# BitUCounter.net
KiCad netlist of a schematic drawn in EAGLE
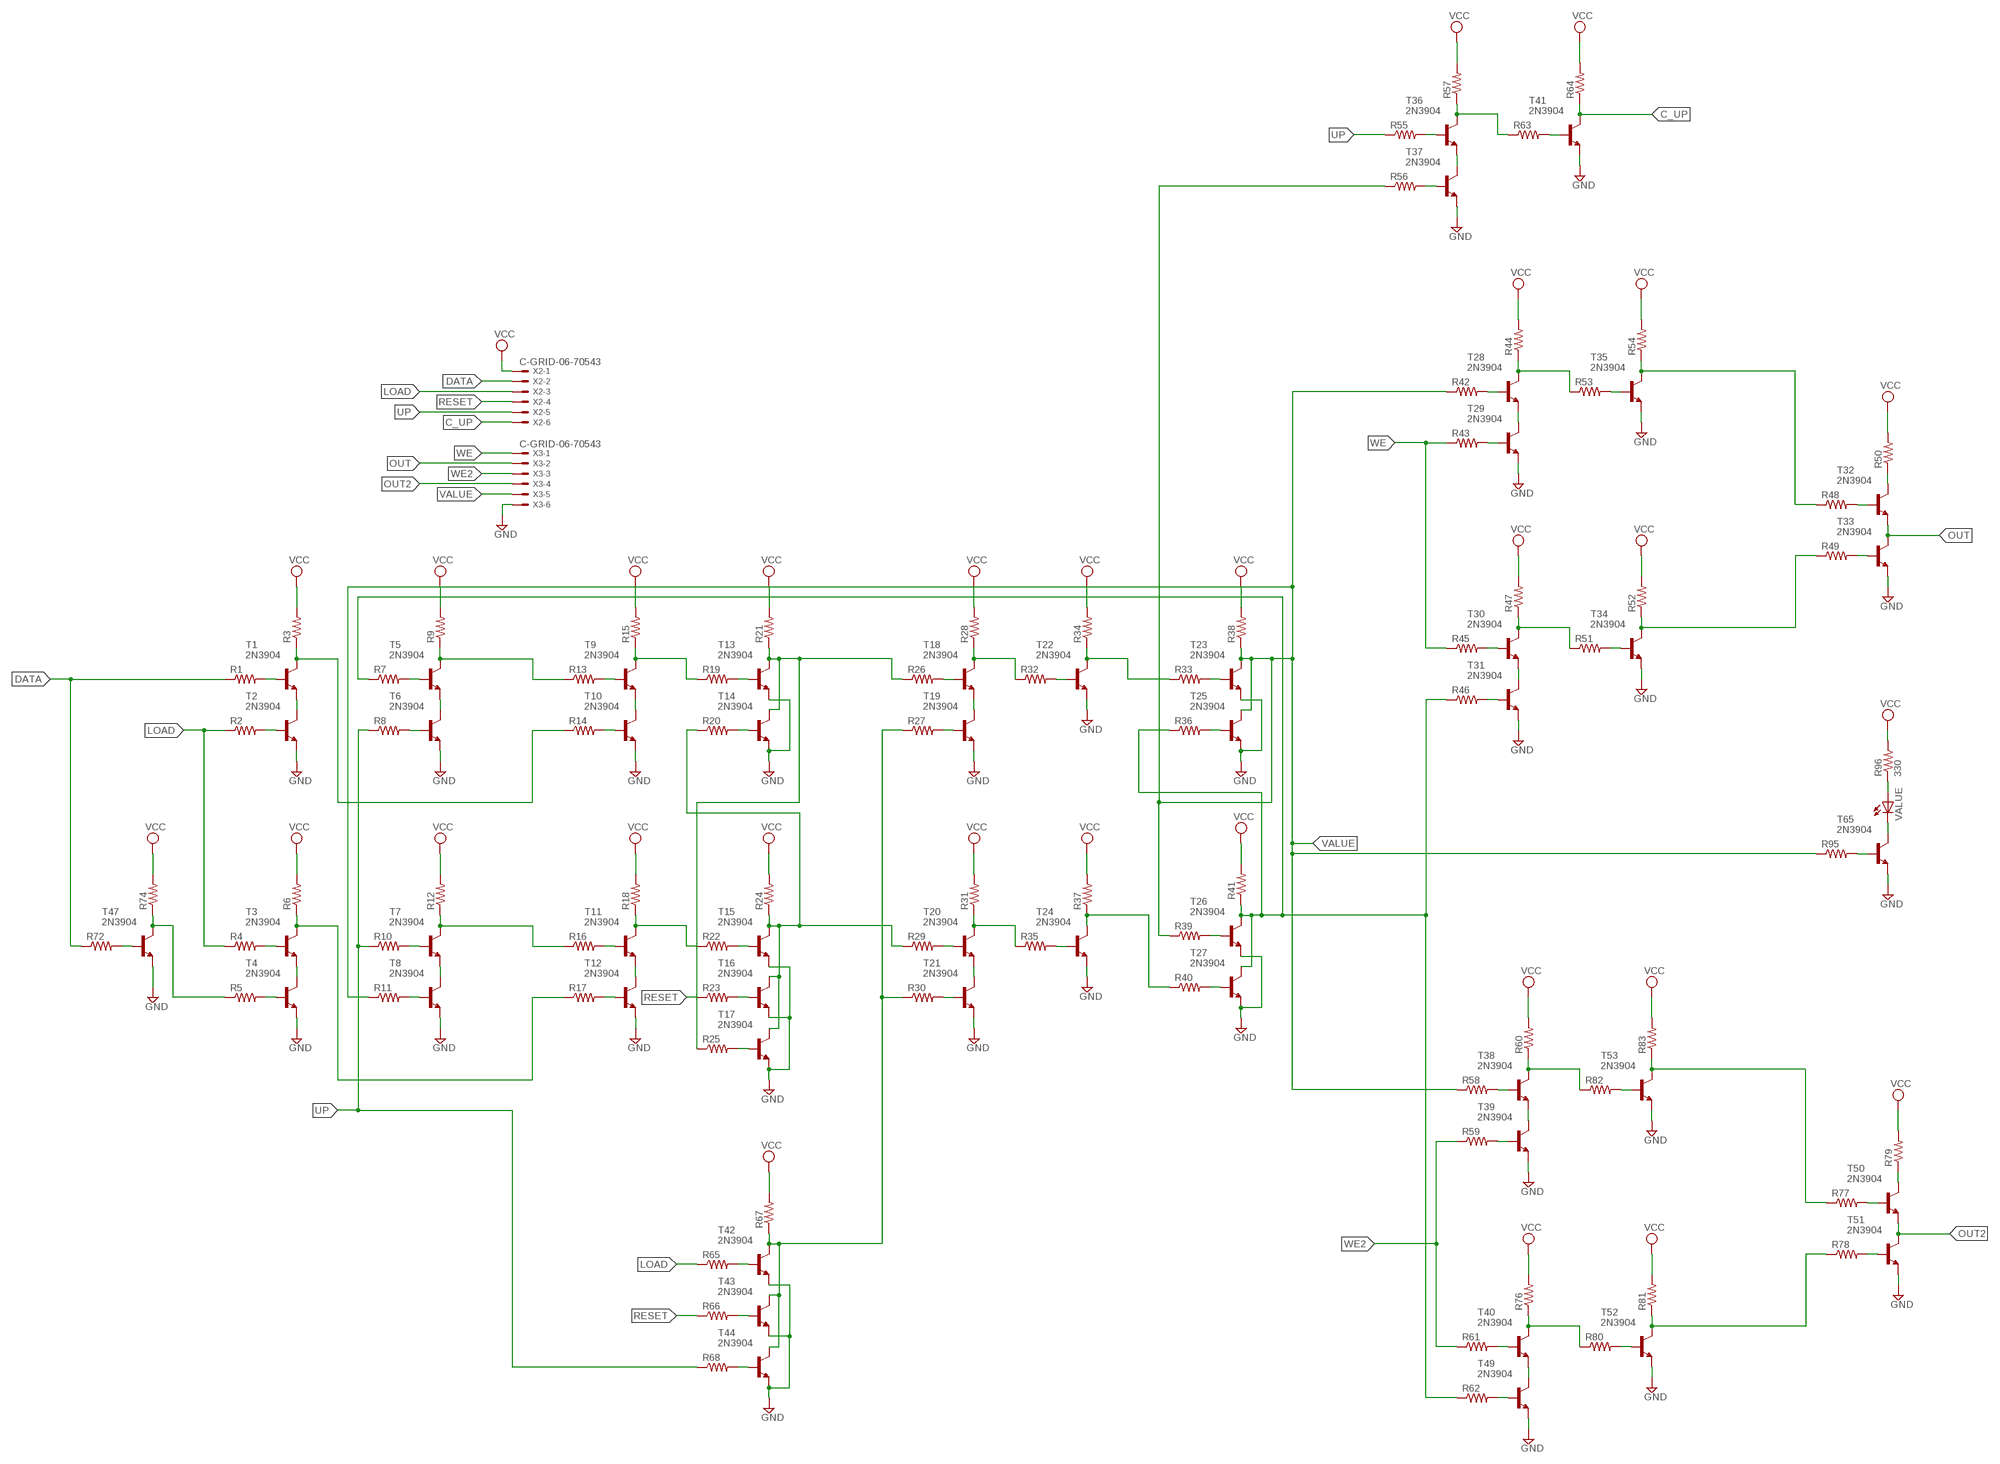
[diagram p0: schematic, sheet 1]

(export (version "E")
  (design (tool "Eeschema 10.0.6"))
  (components
    (comp (ref "R1")
      (value "R-US_0309/10")
      (footprint "eagle-import:0309_10")
      (libsource (lib "eagle-import") (part "R-US_0309/10"))
    )
    (comp (ref "R2")
      (value "R-US_0309/10")
      (footprint "eagle-import:0309_10")
      (libsource (lib "eagle-import") (part "R-US_0309/10"))
    )
    (comp (ref "R3")
      (value "R-US_0309/10")
      (footprint "eagle-import:0309_10")
      (libsource (lib "eagle-import") (part "R-US_0309/10"))
    )
    (comp (ref "R4")
      (value "R-US_0309/10")
      (footprint "eagle-import:0309_10")
      (libsource (lib "eagle-import") (part "R-US_0309/10"))
    )
    (comp (ref "R5")
      (value "R-US_0309/10")
      (footprint "eagle-import:0309_10")
      (libsource (lib "eagle-import") (part "R-US_0309/10"))
    )
    (comp (ref "R6")
      (value "R-US_0309/10")
      (footprint "eagle-import:0309_10")
      (libsource (lib "eagle-import") (part "R-US_0309/10"))
    )
    (comp (ref "R7")
      (value "R-US_0309/10")
      (footprint "eagle-import:0309_10")
      (libsource (lib "eagle-import") (part "R-US_0309/10"))
    )
    (comp (ref "R8")
      (value "R-US_0309/10")
      (footprint "eagle-import:0309_10")
      (libsource (lib "eagle-import") (part "R-US_0309/10"))
    )
    (comp (ref "R9")
      (value "R-US_0309/10")
      (footprint "eagle-import:0309_10")
      (libsource (lib "eagle-import") (part "R-US_0309/10"))
    )
    (comp (ref "R10")
      (value "R-US_0309/10")
      (footprint "eagle-import:0309_10")
      (libsource (lib "eagle-import") (part "R-US_0309/10"))
    )
    (comp (ref "R11")
      (value "R-US_0309/10")
      (footprint "eagle-import:0309_10")
      (libsource (lib "eagle-import") (part "R-US_0309/10"))
    )
    (comp (ref "R12")
      (value "R-US_0309/10")
      (footprint "eagle-import:0309_10")
      (libsource (lib "eagle-import") (part "R-US_0309/10"))
    )
    (comp (ref "R13")
      (value "R-US_0309/10")
      (footprint "eagle-import:0309_10")
      (libsource (lib "eagle-import") (part "R-US_0309/10"))
    )
    (comp (ref "R14")
      (value "R-US_0309/10")
      (footprint "eagle-import:0309_10")
      (libsource (lib "eagle-import") (part "R-US_0309/10"))
    )
    (comp (ref "R15")
      (value "R-US_0309/10")
      (footprint "eagle-import:0309_10")
      (libsource (lib "eagle-import") (part "R-US_0309/10"))
    )
    (comp (ref "R16")
      (value "R-US_0309/10")
      (footprint "eagle-import:0309_10")
      (libsource (lib "eagle-import") (part "R-US_0309/10"))
    )
    (comp (ref "R17")
      (value "R-US_0309/10")
      (footprint "eagle-import:0309_10")
      (libsource (lib "eagle-import") (part "R-US_0309/10"))
    )
    (comp (ref "R18")
      (value "R-US_0309/10")
      (footprint "eagle-import:0309_10")
      (libsource (lib "eagle-import") (part "R-US_0309/10"))
    )
    (comp (ref "R19")
      (value "R-US_0309/10")
      (footprint "eagle-import:0309_10")
      (libsource (lib "eagle-import") (part "R-US_0309/10"))
    )
    (comp (ref "R20")
      (value "R-US_0309/10")
      (footprint "eagle-import:0309_10")
      (libsource (lib "eagle-import") (part "R-US_0309/10"))
    )
    (comp (ref "R21")
      (value "R-US_0309/10")
      (footprint "eagle-import:0309_10")
      (libsource (lib "eagle-import") (part "R-US_0309/10"))
    )
    (comp (ref "R22")
      (value "R-US_0309/10")
      (footprint "eagle-import:0309_10")
      (libsource (lib "eagle-import") (part "R-US_0309/10"))
    )
    (comp (ref "R23")
      (value "R-US_0309/10")
      (footprint "eagle-import:0309_10")
      (libsource (lib "eagle-import") (part "R-US_0309/10"))
    )
    (comp (ref "R24")
      (value "R-US_0309/10")
      (footprint "eagle-import:0309_10")
      (libsource (lib "eagle-import") (part "R-US_0309/10"))
    )
    (comp (ref "R25")
      (value "R-US_0309/10")
      (footprint "eagle-import:0309_10")
      (libsource (lib "eagle-import") (part "R-US_0309/10"))
    )
    (comp (ref "R26")
      (value "R-US_0309/10")
      (footprint "eagle-import:0309_10")
      (libsource (lib "eagle-import") (part "R-US_0309/10"))
    )
    (comp (ref "R27")
      (value "R-US_0309/10")
      (footprint "eagle-import:0309_10")
      (libsource (lib "eagle-import") (part "R-US_0309/10"))
    )
    (comp (ref "R28")
      (value "R-US_0309/10")
      (footprint "eagle-import:0309_10")
      (libsource (lib "eagle-import") (part "R-US_0309/10"))
    )
    (comp (ref "R29")
      (value "R-US_0309/10")
      (footprint "eagle-import:0309_10")
      (libsource (lib "eagle-import") (part "R-US_0309/10"))
    )
    (comp (ref "R30")
      (value "R-US_0309/10")
      (footprint "eagle-import:0309_10")
      (libsource (lib "eagle-import") (part "R-US_0309/10"))
    )
    (comp (ref "R31")
      (value "R-US_0309/10")
      (footprint "eagle-import:0309_10")
      (libsource (lib "eagle-import") (part "R-US_0309/10"))
    )
    (comp (ref "R32")
      (value "R-US_0309/10")
      (footprint "eagle-import:0309_10")
      (libsource (lib "eagle-import") (part "R-US_0309/10"))
    )
    (comp (ref "R33")
      (value "R-US_0309/10")
      (footprint "eagle-import:0309_10")
      (libsource (lib "eagle-import") (part "R-US_0309/10"))
    )
    (comp (ref "R34")
      (value "R-US_0309/10")
      (footprint "eagle-import:0309_10")
      (libsource (lib "eagle-import") (part "R-US_0309/10"))
    )
    (comp (ref "R35")
      (value "R-US_0309/10")
      (footprint "eagle-import:0309_10")
      (libsource (lib "eagle-import") (part "R-US_0309/10"))
    )
    (comp (ref "R36")
      (value "R-US_0309/10")
      (footprint "eagle-import:0309_10")
      (libsource (lib "eagle-import") (part "R-US_0309/10"))
    )
    (comp (ref "R37")
      (value "R-US_0309/10")
      (footprint "eagle-import:0309_10")
      (libsource (lib "eagle-import") (part "R-US_0309/10"))
    )
    (comp (ref "R38")
      (value "R-US_0309/10")
      (footprint "eagle-import:0309_10")
      (libsource (lib "eagle-import") (part "R-US_0309/10"))
    )
    (comp (ref "R39")
      (value "R-US_0309/10")
      (footprint "eagle-import:0309_10")
      (libsource (lib "eagle-import") (part "R-US_0309/10"))
    )
    (comp (ref "R40")
      (value "R-US_0309/10")
      (footprint "eagle-import:0309_10")
      (libsource (lib "eagle-import") (part "R-US_0309/10"))
    )
    (comp (ref "R41")
      (value "R-US_0309/10")
      (footprint "eagle-import:0309_10")
      (libsource (lib "eagle-import") (part "R-US_0309/10"))
    )
    (comp (ref "R42")
      (value "R-US_0309/10")
      (footprint "eagle-import:0309_10")
      (libsource (lib "eagle-import") (part "R-US_0309/10"))
    )
    (comp (ref "R43")
      (value "R-US_0309/10")
      (footprint "eagle-import:0309_10")
      (libsource (lib "eagle-import") (part "R-US_0309/10"))
    )
    (comp (ref "R44")
      (value "R-US_0309/10")
      (footprint "eagle-import:0309_10")
      (libsource (lib "eagle-import") (part "R-US_0309/10"))
    )
    (comp (ref "R45")
      (value "R-US_0309/10")
      (footprint "eagle-import:0309_10")
      (libsource (lib "eagle-import") (part "R-US_0309/10"))
    )
    (comp (ref "R46")
      (value "R-US_0309/10")
      (footprint "eagle-import:0309_10")
      (libsource (lib "eagle-import") (part "R-US_0309/10"))
    )
    (comp (ref "R47")
      (value "R-US_0309/10")
      (footprint "eagle-import:0309_10")
      (libsource (lib "eagle-import") (part "R-US_0309/10"))
    )
    (comp (ref "R48")
      (value "R-US_0309/10")
      (footprint "eagle-import:0309_10")
      (libsource (lib "eagle-import") (part "R-US_0309/10"))
    )
    (comp (ref "R49")
      (value "R-US_0309/10")
      (footprint "eagle-import:0309_10")
      (libsource (lib "eagle-import") (part "R-US_0309/10"))
    )
    (comp (ref "R50")
      (value "R-US_0309/10")
      (footprint "eagle-import:0309_10")
      (libsource (lib "eagle-import") (part "R-US_0309/10"))
    )
    (comp (ref "R51")
      (value "R-US_0309/10")
      (footprint "eagle-import:0309_10")
      (libsource (lib "eagle-import") (part "R-US_0309/10"))
    )
    (comp (ref "R52")
      (value "R-US_0309/10")
      (footprint "eagle-import:0309_10")
      (libsource (lib "eagle-import") (part "R-US_0309/10"))
    )
    (comp (ref "R53")
      (value "R-US_0309/10")
      (footprint "eagle-import:0309_10")
      (libsource (lib "eagle-import") (part "R-US_0309/10"))
    )
    (comp (ref "R54")
      (value "R-US_0309/10")
      (footprint "eagle-import:0309_10")
      (libsource (lib "eagle-import") (part "R-US_0309/10"))
    )
    (comp (ref "R55")
      (value "R-US_0309/10")
      (footprint "eagle-import:0309_10")
      (libsource (lib "eagle-import") (part "R-US_0309/10"))
    )
    (comp (ref "R56")
      (value "R-US_0309/10")
      (footprint "eagle-import:0309_10")
      (libsource (lib "eagle-import") (part "R-US_0309/10"))
    )
    (comp (ref "R57")
      (value "R-US_0309/10")
      (footprint "eagle-import:0309_10")
      (libsource (lib "eagle-import") (part "R-US_0309/10"))
    )
    (comp (ref "R58")
      (value "R-US_0309/10")
      (footprint "eagle-import:0309_10")
      (libsource (lib "eagle-import") (part "R-US_0309/10"))
    )
    (comp (ref "R59")
      (value "R-US_0309/10")
      (footprint "eagle-import:0309_10")
      (libsource (lib "eagle-import") (part "R-US_0309/10"))
    )
    (comp (ref "R60")
      (value "R-US_0309/10")
      (footprint "eagle-import:0309_10")
      (libsource (lib "eagle-import") (part "R-US_0309/10"))
    )
    (comp (ref "R61")
      (value "R-US_0309/10")
      (footprint "eagle-import:0309_10")
      (libsource (lib "eagle-import") (part "R-US_0309/10"))
    )
    (comp (ref "R62")
      (value "R-US_0309/10")
      (footprint "eagle-import:0309_10")
      (libsource (lib "eagle-import") (part "R-US_0309/10"))
    )
    (comp (ref "R63")
      (value "R-US_0309/10")
      (footprint "eagle-import:0309_10")
      (libsource (lib "eagle-import") (part "R-US_0309/10"))
    )
    (comp (ref "R64")
      (value "R-US_0309/10")
      (footprint "eagle-import:0309_10")
      (libsource (lib "eagle-import") (part "R-US_0309/10"))
    )
    (comp (ref "R65")
      (value "R-US_0309/10")
      (footprint "eagle-import:0309_10")
      (libsource (lib "eagle-import") (part "R-US_0309/10"))
    )
    (comp (ref "R66")
      (value "R-US_0309/10")
      (footprint "eagle-import:0309_10")
      (libsource (lib "eagle-import") (part "R-US_0309/10"))
    )
    (comp (ref "R67")
      (value "R-US_0309/10")
      (footprint "eagle-import:0309_10")
      (libsource (lib "eagle-import") (part "R-US_0309/10"))
    )
    (comp (ref "R68")
      (value "R-US_0309/10")
      (footprint "eagle-import:0309_10")
      (libsource (lib "eagle-import") (part "R-US_0309/10"))
    )
    (comp (ref "R72")
      (value "R-US_0309/10")
      (footprint "eagle-import:0309_10")
      (libsource (lib "eagle-import") (part "R-US_0309/10"))
    )
    (comp (ref "R74")
      (value "R-US_0309/10")
      (footprint "eagle-import:0309_10")
      (libsource (lib "eagle-import") (part "R-US_0309/10"))
    )
    (comp (ref "R76")
      (value "R-US_0309/10")
      (footprint "eagle-import:0309_10")
      (libsource (lib "eagle-import") (part "R-US_0309/10"))
    )
    (comp (ref "R77")
      (value "R-US_0309/10")
      (footprint "eagle-import:0309_10")
      (libsource (lib "eagle-import") (part "R-US_0309/10"))
    )
    (comp (ref "R78")
      (value "R-US_0309/10")
      (footprint "eagle-import:0309_10")
      (libsource (lib "eagle-import") (part "R-US_0309/10"))
    )
    (comp (ref "R79")
      (value "R-US_0309/10")
      (footprint "eagle-import:0309_10")
      (libsource (lib "eagle-import") (part "R-US_0309/10"))
    )
    (comp (ref "R80")
      (value "R-US_0309/10")
      (footprint "eagle-import:0309_10")
      (libsource (lib "eagle-import") (part "R-US_0309/10"))
    )
    (comp (ref "R81")
      (value "R-US_0309/10")
      (footprint "eagle-import:0309_10")
      (libsource (lib "eagle-import") (part "R-US_0309/10"))
    )
    (comp (ref "R82")
      (value "R-US_0309/10")
      (footprint "eagle-import:0309_10")
      (libsource (lib "eagle-import") (part "R-US_0309/10"))
    )
    (comp (ref "R83")
      (value "R-US_0309/10")
      (footprint "eagle-import:0309_10")
      (libsource (lib "eagle-import") (part "R-US_0309/10"))
    )
    (comp (ref "R95")
      (value "R-US_0309/10")
      (footprint "eagle-import:0309_10")
      (libsource (lib "eagle-import") (part "R-US_0309/10"))
    )
    (comp (ref "R96")
      (value "330")
      (footprint "eagle-import:0309_10")
      (libsource (lib "eagle-import") (part "R-US_0309/10"))
    )
    (comp (ref "T1")
      (value "2N3904")
      (footprint "eagle-import:TO92")
      (libsource (lib "eagle-import") (part "2N3904"))
    )
    (comp (ref "T2")
      (value "2N3904")
      (footprint "eagle-import:TO92")
      (libsource (lib "eagle-import") (part "2N3904"))
    )
    (comp (ref "T3")
      (value "2N3904")
      (footprint "eagle-import:TO92")
      (libsource (lib "eagle-import") (part "2N3904"))
    )
    (comp (ref "T4")
      (value "2N3904")
      (footprint "eagle-import:TO92")
      (libsource (lib "eagle-import") (part "2N3904"))
    )
    (comp (ref "T5")
      (value "2N3904")
      (footprint "eagle-import:TO92")
      (libsource (lib "eagle-import") (part "2N3904"))
    )
    (comp (ref "T6")
      (value "2N3904")
      (footprint "eagle-import:TO92")
      (libsource (lib "eagle-import") (part "2N3904"))
    )
    (comp (ref "T7")
      (value "2N3904")
      (footprint "eagle-import:TO92")
      (libsource (lib "eagle-import") (part "2N3904"))
    )
    (comp (ref "T8")
      (value "2N3904")
      (footprint "eagle-import:TO92")
      (libsource (lib "eagle-import") (part "2N3904"))
    )
    (comp (ref "T9")
      (value "2N3904")
      (footprint "eagle-import:TO92")
      (libsource (lib "eagle-import") (part "2N3904"))
    )
    (comp (ref "T10")
      (value "2N3904")
      (footprint "eagle-import:TO92")
      (libsource (lib "eagle-import") (part "2N3904"))
    )
    (comp (ref "T11")
      (value "2N3904")
      (footprint "eagle-import:TO92")
      (libsource (lib "eagle-import") (part "2N3904"))
    )
    (comp (ref "T12")
      (value "2N3904")
      (footprint "eagle-import:TO92")
      (libsource (lib "eagle-import") (part "2N3904"))
    )
    (comp (ref "T13")
      (value "2N3904")
      (footprint "eagle-import:TO92")
      (libsource (lib "eagle-import") (part "2N3904"))
    )
    (comp (ref "T14")
      (value "2N3904")
      (footprint "eagle-import:TO92")
      (libsource (lib "eagle-import") (part "2N3904"))
    )
    (comp (ref "T15")
      (value "2N3904")
      (footprint "eagle-import:TO92")
      (libsource (lib "eagle-import") (part "2N3904"))
    )
    (comp (ref "T16")
      (value "2N3904")
      (footprint "eagle-import:TO92")
      (libsource (lib "eagle-import") (part "2N3904"))
    )
    (comp (ref "T17")
      (value "2N3904")
      (footprint "eagle-import:TO92")
      (libsource (lib "eagle-import") (part "2N3904"))
    )
    (comp (ref "T18")
      (value "2N3904")
      (footprint "eagle-import:TO92")
      (libsource (lib "eagle-import") (part "2N3904"))
    )
    (comp (ref "T19")
      (value "2N3904")
      (footprint "eagle-import:TO92")
      (libsource (lib "eagle-import") (part "2N3904"))
    )
    (comp (ref "T20")
      (value "2N3904")
      (footprint "eagle-import:TO92")
      (libsource (lib "eagle-import") (part "2N3904"))
    )
    (comp (ref "T21")
      (value "2N3904")
      (footprint "eagle-import:TO92")
      (libsource (lib "eagle-import") (part "2N3904"))
    )
    (comp (ref "T22")
      (value "2N3904")
      (footprint "eagle-import:TO92")
      (libsource (lib "eagle-import") (part "2N3904"))
    )
    (comp (ref "T23")
      (value "2N3904")
      (footprint "eagle-import:TO92")
      (libsource (lib "eagle-import") (part "2N3904"))
    )
    (comp (ref "T24")
      (value "2N3904")
      (footprint "eagle-import:TO92")
      (libsource (lib "eagle-import") (part "2N3904"))
    )
    (comp (ref "T25")
      (value "2N3904")
      (footprint "eagle-import:TO92")
      (libsource (lib "eagle-import") (part "2N3904"))
    )
    (comp (ref "T26")
      (value "2N3904")
      (footprint "eagle-import:TO92")
      (libsource (lib "eagle-import") (part "2N3904"))
    )
    (comp (ref "T27")
      (value "2N3904")
      (footprint "eagle-import:TO92")
      (libsource (lib "eagle-import") (part "2N3904"))
    )
    (comp (ref "T28")
      (value "2N3904")
      (footprint "eagle-import:TO92")
      (libsource (lib "eagle-import") (part "2N3904"))
    )
    (comp (ref "T29")
      (value "2N3904")
      (footprint "eagle-import:TO92")
      (libsource (lib "eagle-import") (part "2N3904"))
    )
    (comp (ref "T30")
      (value "2N3904")
      (footprint "eagle-import:TO92")
      (libsource (lib "eagle-import") (part "2N3904"))
    )
    (comp (ref "T31")
      (value "2N3904")
      (footprint "eagle-import:TO92")
      (libsource (lib "eagle-import") (part "2N3904"))
    )
    (comp (ref "T32")
      (value "2N3904")
      (footprint "eagle-import:TO92")
      (libsource (lib "eagle-import") (part "2N3904"))
    )
    (comp (ref "T33")
      (value "2N3904")
      (footprint "eagle-import:TO92")
      (libsource (lib "eagle-import") (part "2N3904"))
    )
    (comp (ref "T34")
      (value "2N3904")
      (footprint "eagle-import:TO92")
      (libsource (lib "eagle-import") (part "2N3904"))
    )
    (comp (ref "T35")
      (value "2N3904")
      (footprint "eagle-import:TO92")
      (libsource (lib "eagle-import") (part "2N3904"))
    )
    (comp (ref "T36")
      (value "2N3904")
      (footprint "eagle-import:TO92")
      (libsource (lib "eagle-import") (part "2N3904"))
    )
    (comp (ref "T37")
      (value "2N3904")
      (footprint "eagle-import:TO92")
      (libsource (lib "eagle-import") (part "2N3904"))
    )
    (comp (ref "T38")
      (value "2N3904")
      (footprint "eagle-import:TO92")
      (libsource (lib "eagle-import") (part "2N3904"))
    )
    (comp (ref "T39")
      (value "2N3904")
      (footprint "eagle-import:TO92")
      (libsource (lib "eagle-import") (part "2N3904"))
    )
    (comp (ref "T40")
      (value "2N3904")
      (footprint "eagle-import:TO92")
      (libsource (lib "eagle-import") (part "2N3904"))
    )
    (comp (ref "T41")
      (value "2N3904")
      (footprint "eagle-import:TO92")
      (libsource (lib "eagle-import") (part "2N3904"))
    )
    (comp (ref "T42")
      (value "2N3904")
      (footprint "eagle-import:TO92")
      (libsource (lib "eagle-import") (part "2N3904"))
    )
    (comp (ref "T43")
      (value "2N3904")
      (footprint "eagle-import:TO92")
      (libsource (lib "eagle-import") (part "2N3904"))
    )
    (comp (ref "T44")
      (value "2N3904")
      (footprint "eagle-import:TO92")
      (libsource (lib "eagle-import") (part "2N3904"))
    )
    (comp (ref "T47")
      (value "2N3904")
      (footprint "eagle-import:TO92")
      (libsource (lib "eagle-import") (part "2N3904"))
    )
    (comp (ref "T49")
      (value "2N3904")
      (footprint "eagle-import:TO92")
      (libsource (lib "eagle-import") (part "2N3904"))
    )
    (comp (ref "T50")
      (value "2N3904")
      (footprint "eagle-import:TO92")
      (libsource (lib "eagle-import") (part "2N3904"))
    )
    (comp (ref "T51")
      (value "2N3904")
      (footprint "eagle-import:TO92")
      (libsource (lib "eagle-import") (part "2N3904"))
    )
    (comp (ref "T52")
      (value "2N3904")
      (footprint "eagle-import:TO92")
      (libsource (lib "eagle-import") (part "2N3904"))
    )
    (comp (ref "T53")
      (value "2N3904")
      (footprint "eagle-import:TO92")
      (libsource (lib "eagle-import") (part "2N3904"))
    )
    (comp (ref "T65")
      (value "2N3904")
      (footprint "eagle-import:TO92")
      (libsource (lib "eagle-import") (part "2N3904"))
    )
    (comp (ref "VALUE")
      (value "LED5MM")
      (footprint "eagle-import:LED5MM")
      (libsource (lib "eagle-import") (part "LED5MM"))
    )
    (comp (ref "X2")
      (value "C-GRID-06-70543")
      (footprint "eagle-import:70543-06")
      (fields (field (name "MF") "MOLEX"))
      (libsource (lib "eagle-import") (part "C-GRID-06-70543"))
    )
    (comp (ref "X3")
      (value "C-GRID-06-70543")
      (footprint "eagle-import:70543-06")
      (fields (field (name "MF") "MOLEX"))
      (libsource (lib "eagle-import") (part "C-GRID-06-70543"))
    )
  )
  (nets
    (net (code "1") (name "C_UP") (class "Default")
      (node (ref "R64") (pin "1") (pinfunction "1_1") (pintype "passive"))
      (node (ref "T41") (pin "1") (pinfunction "C_1") (pintype "passive"))
      (node (ref "X2") (pin "6") (pinfunction "S_6") (pintype "passive"))
    )
    (net (code "2") (name "DATA") (class "Default")
      (node (ref "R1") (pin "1") (pinfunction "1_1") (pintype "passive"))
      (node (ref "R72") (pin "1") (pinfunction "1_1") (pintype "passive"))
      (node (ref "X2") (pin "2") (pinfunction "S_2") (pintype "passive"))
    )
    (net (code "3") (name "GND") (class "Default")
      (node (ref "T10") (pin "3") (pinfunction "E_3") (pintype "passive"))
      (node (ref "T12") (pin "3") (pinfunction "E_3") (pintype "passive"))
      (node (ref "T13") (pin "3") (pinfunction "E_3") (pintype "passive"))
      (node (ref "T14") (pin "3") (pinfunction "E_3") (pintype "passive"))
      (node (ref "T15") (pin "3") (pinfunction "E_3") (pintype "passive"))
      (node (ref "T16") (pin "3") (pinfunction "E_3") (pintype "passive"))
      (node (ref "T17") (pin "3") (pinfunction "E_3") (pintype "passive"))
      (node (ref "T19") (pin "3") (pinfunction "E_3") (pintype "passive"))
      (node (ref "T2") (pin "3") (pinfunction "E_3") (pintype "passive"))
      (node (ref "T21") (pin "3") (pinfunction "E_3") (pintype "passive"))
      (node (ref "T22") (pin "3") (pinfunction "E_3") (pintype "passive"))
      (node (ref "T23") (pin "3") (pinfunction "E_3") (pintype "passive"))
      (node (ref "T24") (pin "3") (pinfunction "E_3") (pintype "passive"))
      (node (ref "T25") (pin "3") (pinfunction "E_3") (pintype "passive"))
      (node (ref "T26") (pin "3") (pinfunction "E_3") (pintype "passive"))
      (node (ref "T27") (pin "3") (pinfunction "E_3") (pintype "passive"))
      (node (ref "T29") (pin "3") (pinfunction "E_3") (pintype "passive"))
      (node (ref "T31") (pin "3") (pinfunction "E_3") (pintype "passive"))
      (node (ref "T33") (pin "3") (pinfunction "E_3") (pintype "passive"))
      (node (ref "T34") (pin "3") (pinfunction "E_3") (pintype "passive"))
      (node (ref "T35") (pin "3") (pinfunction "E_3") (pintype "passive"))
      (node (ref "T37") (pin "3") (pinfunction "E_3") (pintype "passive"))
      (node (ref "T39") (pin "3") (pinfunction "E_3") (pintype "passive"))
      (node (ref "T4") (pin "3") (pinfunction "E_3") (pintype "passive"))
      (node (ref "T41") (pin "3") (pinfunction "E_3") (pintype "passive"))
      (node (ref "T42") (pin "3") (pinfunction "E_3") (pintype "passive"))
      (node (ref "T43") (pin "3") (pinfunction "E_3") (pintype "passive"))
      (node (ref "T44") (pin "3") (pinfunction "E_3") (pintype "passive"))
      (node (ref "T47") (pin "3") (pinfunction "E_3") (pintype "passive"))
      (node (ref "T49") (pin "3") (pinfunction "E_3") (pintype "passive"))
      (node (ref "T51") (pin "3") (pinfunction "E_3") (pintype "passive"))
      (node (ref "T52") (pin "3") (pinfunction "E_3") (pintype "passive"))
      (node (ref "T53") (pin "3") (pinfunction "E_3") (pintype "passive"))
      (node (ref "T6") (pin "3") (pinfunction "E_3") (pintype "passive"))
      (node (ref "T65") (pin "3") (pinfunction "E_3") (pintype "passive"))
      (node (ref "T8") (pin "3") (pinfunction "E_3") (pintype "passive"))
      (node (ref "X3") (pin "6") (pinfunction "S_6") (pintype "passive"))
    )
    (net (code "4") (name "LOAD") (class "Default")
      (node (ref "R2") (pin "1") (pinfunction "1_1") (pintype "passive"))
      (node (ref "R4") (pin "1") (pinfunction "1_1") (pintype "passive"))
      (node (ref "R65") (pin "1") (pinfunction "1_1") (pintype "passive"))
      (node (ref "X2") (pin "3") (pinfunction "S_3") (pintype "passive"))
    )
    (net (code "5") (name "Net-(R96-Pad1)") (class "Default")
      (node (ref "R96") (pin "1") (pinfunction "1_1") (pintype "passive"))
      (node (ref "VALUE") (pin "A") (pinfunction "A_A") (pintype "passive"))
    )
    (net (code "6") (name "Net-(T1-B)") (class "Default")
      (node (ref "R1") (pin "2") (pinfunction "2_2") (pintype "passive"))
      (node (ref "T1") (pin "2") (pinfunction "B_2") (pintype "passive"))
    )
    (net (code "7") (name "Net-(T1-C)") (class "Default")
      (node (ref "R14") (pin "1") (pinfunction "1_1") (pintype "passive"))
      (node (ref "R3") (pin "1") (pinfunction "1_1") (pintype "passive"))
      (node (ref "T1") (pin "1") (pinfunction "C_1") (pintype "passive"))
    )
    (net (code "8") (name "Net-(T1-E)") (class "Default")
      (node (ref "T1") (pin "3") (pinfunction "E_3") (pintype "passive"))
      (node (ref "T2") (pin "1") (pinfunction "C_1") (pintype "passive"))
    )
    (net (code "9") (name "Net-(T2-B)") (class "Default")
      (node (ref "R2") (pin "2") (pinfunction "2_2") (pintype "passive"))
      (node (ref "T2") (pin "2") (pinfunction "B_2") (pintype "passive"))
    )
    (net (code "10") (name "Net-(T3-B)") (class "Default")
      (node (ref "R4") (pin "2") (pinfunction "2_2") (pintype "passive"))
      (node (ref "T3") (pin "2") (pinfunction "B_2") (pintype "passive"))
    )
    (net (code "11") (name "Net-(T3-C)") (class "Default")
      (node (ref "R17") (pin "1") (pinfunction "1_1") (pintype "passive"))
      (node (ref "R6") (pin "1") (pinfunction "1_1") (pintype "passive"))
      (node (ref "T3") (pin "1") (pinfunction "C_1") (pintype "passive"))
    )
    (net (code "12") (name "Net-(T3-E)") (class "Default")
      (node (ref "T3") (pin "3") (pinfunction "E_3") (pintype "passive"))
      (node (ref "T4") (pin "1") (pinfunction "C_1") (pintype "passive"))
    )
    (net (code "13") (name "Net-(T4-B)") (class "Default")
      (node (ref "R5") (pin "2") (pinfunction "2_2") (pintype "passive"))
      (node (ref "T4") (pin "2") (pinfunction "B_2") (pintype "passive"))
    )
    (net (code "14") (name "Net-(T5-B)") (class "Default")
      (node (ref "R7") (pin "2") (pinfunction "2_2") (pintype "passive"))
      (node (ref "T5") (pin "2") (pinfunction "B_2") (pintype "passive"))
    )
    (net (code "15") (name "Net-(T5-C)") (class "Default")
      (node (ref "R13") (pin "1") (pinfunction "1_1") (pintype "passive"))
      (node (ref "R9") (pin "1") (pinfunction "1_1") (pintype "passive"))
      (node (ref "T5") (pin "1") (pinfunction "C_1") (pintype "passive"))
    )
    (net (code "16") (name "Net-(T5-E)") (class "Default")
      (node (ref "T5") (pin "3") (pinfunction "E_3") (pintype "passive"))
      (node (ref "T6") (pin "1") (pinfunction "C_1") (pintype "passive"))
    )
    (net (code "17") (name "Net-(T6-B)") (class "Default")
      (node (ref "R8") (pin "2") (pinfunction "2_2") (pintype "passive"))
      (node (ref "T6") (pin "2") (pinfunction "B_2") (pintype "passive"))
    )
    (net (code "18") (name "Net-(T7-B)") (class "Default")
      (node (ref "R10") (pin "2") (pinfunction "2_2") (pintype "passive"))
      (node (ref "T7") (pin "2") (pinfunction "B_2") (pintype "passive"))
    )
    (net (code "19") (name "Net-(T7-C)") (class "Default")
      (node (ref "R12") (pin "1") (pinfunction "1_1") (pintype "passive"))
      (node (ref "R16") (pin "1") (pinfunction "1_1") (pintype "passive"))
      (node (ref "T7") (pin "1") (pinfunction "C_1") (pintype "passive"))
    )
    (net (code "20") (name "Net-(T7-E)") (class "Default")
      (node (ref "T7") (pin "3") (pinfunction "E_3") (pintype "passive"))
      (node (ref "T8") (pin "1") (pinfunction "C_1") (pintype "passive"))
    )
    (net (code "21") (name "Net-(T8-B)") (class "Default")
      (node (ref "R11") (pin "2") (pinfunction "2_2") (pintype "passive"))
      (node (ref "T8") (pin "2") (pinfunction "B_2") (pintype "passive"))
    )
    (net (code "22") (name "Net-(T9-B)") (class "Default")
      (node (ref "R13") (pin "2") (pinfunction "2_2") (pintype "passive"))
      (node (ref "T9") (pin "2") (pinfunction "B_2") (pintype "passive"))
    )
    (net (code "23") (name "Net-(T9-C)") (class "Default")
      (node (ref "R15") (pin "1") (pinfunction "1_1") (pintype "passive"))
      (node (ref "R19") (pin "1") (pinfunction "1_1") (pintype "passive"))
      (node (ref "T9") (pin "1") (pinfunction "C_1") (pintype "passive"))
    )
    (net (code "24") (name "Net-(T10-B)") (class "Default")
      (node (ref "R14") (pin "2") (pinfunction "2_2") (pintype "passive"))
      (node (ref "T10") (pin "2") (pinfunction "B_2") (pintype "passive"))
    )
    (net (code "25") (name "Net-(T10-C)") (class "Default")
      (node (ref "T10") (pin "1") (pinfunction "C_1") (pintype "passive"))
      (node (ref "T9") (pin "3") (pinfunction "E_3") (pintype "passive"))
    )
    (net (code "26") (name "Net-(T11-B)") (class "Default")
      (node (ref "R16") (pin "2") (pinfunction "2_2") (pintype "passive"))
      (node (ref "T11") (pin "2") (pinfunction "B_2") (pintype "passive"))
    )
    (net (code "27") (name "Net-(T11-C)") (class "Default")
      (node (ref "R18") (pin "1") (pinfunction "1_1") (pintype "passive"))
      (node (ref "R22") (pin "1") (pinfunction "1_1") (pintype "passive"))
      (node (ref "T11") (pin "1") (pinfunction "C_1") (pintype "passive"))
    )
    (net (code "28") (name "Net-(T11-E)") (class "Default")
      (node (ref "T11") (pin "3") (pinfunction "E_3") (pintype "passive"))
      (node (ref "T12") (pin "1") (pinfunction "C_1") (pintype "passive"))
    )
    (net (code "29") (name "Net-(T12-B)") (class "Default")
      (node (ref "R17") (pin "2") (pinfunction "2_2") (pintype "passive"))
      (node (ref "T12") (pin "2") (pinfunction "B_2") (pintype "passive"))
    )
    (net (code "30") (name "Net-(T13-B)") (class "Default")
      (node (ref "R19") (pin "2") (pinfunction "2_2") (pintype "passive"))
      (node (ref "T13") (pin "2") (pinfunction "B_2") (pintype "passive"))
    )
    (net (code "31") (name "Net-(T13-C)") (class "Default")
      (node (ref "R21") (pin "1") (pinfunction "1_1") (pintype "passive"))
      (node (ref "R25") (pin "1") (pinfunction "1_1") (pintype "passive"))
      (node (ref "R26") (pin "1") (pinfunction "1_1") (pintype "passive"))
      (node (ref "T13") (pin "1") (pinfunction "C_1") (pintype "passive"))
      (node (ref "T14") (pin "1") (pinfunction "C_1") (pintype "passive"))
    )
    (net (code "32") (name "Net-(T14-B)") (class "Default")
      (node (ref "R20") (pin "2") (pinfunction "2_2") (pintype "passive"))
      (node (ref "T14") (pin "2") (pinfunction "B_2") (pintype "passive"))
    )
    (net (code "33") (name "Net-(T15-B)") (class "Default")
      (node (ref "R22") (pin "2") (pinfunction "2_2") (pintype "passive"))
      (node (ref "T15") (pin "2") (pinfunction "B_2") (pintype "passive"))
    )
    (net (code "34") (name "Net-(T15-C)") (class "Default")
      (node (ref "R20") (pin "1") (pinfunction "1_1") (pintype "passive"))
      (node (ref "R24") (pin "1") (pinfunction "1_1") (pintype "passive"))
      (node (ref "R29") (pin "1") (pinfunction "1_1") (pintype "passive"))
      (node (ref "T15") (pin "1") (pinfunction "C_1") (pintype "passive"))
      (node (ref "T16") (pin "1") (pinfunction "C_1") (pintype "passive"))
      (node (ref "T17") (pin "1") (pinfunction "C_1") (pintype "passive"))
    )
    (net (code "35") (name "Net-(T16-B)") (class "Default")
      (node (ref "R23") (pin "2") (pinfunction "2_2") (pintype "passive"))
      (node (ref "T16") (pin "2") (pinfunction "B_2") (pintype "passive"))
    )
    (net (code "36") (name "Net-(T17-B)") (class "Default")
      (node (ref "R25") (pin "2") (pinfunction "2_2") (pintype "passive"))
      (node (ref "T17") (pin "2") (pinfunction "B_2") (pintype "passive"))
    )
    (net (code "37") (name "Net-(T18-B)") (class "Default")
      (node (ref "R26") (pin "2") (pinfunction "2_2") (pintype "passive"))
      (node (ref "T18") (pin "2") (pinfunction "B_2") (pintype "passive"))
    )
    (net (code "38") (name "Net-(T18-C)") (class "Default")
      (node (ref "R28") (pin "1") (pinfunction "1_1") (pintype "passive"))
      (node (ref "R32") (pin "1") (pinfunction "1_1") (pintype "passive"))
      (node (ref "T18") (pin "1") (pinfunction "C_1") (pintype "passive"))
    )
    (net (code "39") (name "Net-(T18-E)") (class "Default")
      (node (ref "T18") (pin "3") (pinfunction "E_3") (pintype "passive"))
      (node (ref "T19") (pin "1") (pinfunction "C_1") (pintype "passive"))
    )
    (net (code "40") (name "Net-(T19-B)") (class "Default")
      (node (ref "R27") (pin "2") (pinfunction "2_2") (pintype "passive"))
      (node (ref "T19") (pin "2") (pinfunction "B_2") (pintype "passive"))
    )
    (net (code "41") (name "Net-(T20-B)") (class "Default")
      (node (ref "R29") (pin "2") (pinfunction "2_2") (pintype "passive"))
      (node (ref "T20") (pin "2") (pinfunction "B_2") (pintype "passive"))
    )
    (net (code "42") (name "Net-(T20-C)") (class "Default")
      (node (ref "R31") (pin "1") (pinfunction "1_1") (pintype "passive"))
      (node (ref "R35") (pin "1") (pinfunction "1_1") (pintype "passive"))
      (node (ref "T20") (pin "1") (pinfunction "C_1") (pintype "passive"))
    )
    (net (code "43") (name "Net-(T20-E)") (class "Default")
      (node (ref "T20") (pin "3") (pinfunction "E_3") (pintype "passive"))
      (node (ref "T21") (pin "1") (pinfunction "C_1") (pintype "passive"))
    )
    (net (code "44") (name "Net-(T21-B)") (class "Default")
      (node (ref "R30") (pin "2") (pinfunction "2_2") (pintype "passive"))
      (node (ref "T21") (pin "2") (pinfunction "B_2") (pintype "passive"))
    )
    (net (code "45") (name "Net-(T22-B)") (class "Default")
      (node (ref "R32") (pin "2") (pinfunction "2_2") (pintype "passive"))
      (node (ref "T22") (pin "2") (pinfunction "B_2") (pintype "passive"))
    )
    (net (code "46") (name "Net-(T22-C)") (class "Default")
      (node (ref "R33") (pin "1") (pinfunction "1_1") (pintype "passive"))
      (node (ref "R34") (pin "1") (pinfunction "1_1") (pintype "passive"))
      (node (ref "T22") (pin "1") (pinfunction "C_1") (pintype "passive"))
    )
    (net (code "47") (name "Net-(T23-B)") (class "Default")
      (node (ref "R33") (pin "2") (pinfunction "2_2") (pintype "passive"))
      (node (ref "T23") (pin "2") (pinfunction "B_2") (pintype "passive"))
    )
    (net (code "48") (name "Net-(T24-B)") (class "Default")
      (node (ref "R35") (pin "2") (pinfunction "2_2") (pintype "passive"))
      (node (ref "T24") (pin "2") (pinfunction "B_2") (pintype "passive"))
    )
    (net (code "49") (name "Net-(T24-C)") (class "Default")
      (node (ref "R37") (pin "1") (pinfunction "1_1") (pintype "passive"))
      (node (ref "R40") (pin "1") (pinfunction "1_1") (pintype "passive"))
      (node (ref "T24") (pin "1") (pinfunction "C_1") (pintype "passive"))
    )
    (net (code "50") (name "Net-(T25-B)") (class "Default")
      (node (ref "R36") (pin "2") (pinfunction "2_2") (pintype "passive"))
      (node (ref "T25") (pin "2") (pinfunction "B_2") (pintype "passive"))
    )
    (net (code "51") (name "Net-(T26-B)") (class "Default")
      (node (ref "R39") (pin "2") (pinfunction "2_2") (pintype "passive"))
      (node (ref "T26") (pin "2") (pinfunction "B_2") (pintype "passive"))
    )
    (net (code "52") (name "Net-(T26-C)") (class "Default")
      (node (ref "R36") (pin "1") (pinfunction "1_1") (pintype "passive"))
      (node (ref "R41") (pin "1") (pinfunction "1_1") (pintype "passive"))
      (node (ref "R46") (pin "1") (pinfunction "1_1") (pintype "passive"))
      (node (ref "R62") (pin "1") (pinfunction "1_1") (pintype "passive"))
      (node (ref "R7") (pin "1") (pinfunction "1_1") (pintype "passive"))
      (node (ref "T26") (pin "1") (pinfunction "C_1") (pintype "passive"))
      (node (ref "T27") (pin "1") (pinfunction "C_1") (pintype "passive"))
    )
    (net (code "53") (name "Net-(T27-B)") (class "Default")
      (node (ref "R40") (pin "2") (pinfunction "2_2") (pintype "passive"))
      (node (ref "T27") (pin "2") (pinfunction "B_2") (pintype "passive"))
    )
    (net (code "54") (name "Net-(T28-B)") (class "Default")
      (node (ref "R42") (pin "2") (pinfunction "2_2") (pintype "passive"))
      (node (ref "T28") (pin "2") (pinfunction "B_2") (pintype "passive"))
    )
    (net (code "55") (name "Net-(T28-C)") (class "Default")
      (node (ref "R44") (pin "1") (pinfunction "1_1") (pintype "passive"))
      (node (ref "R53") (pin "1") (pinfunction "1_1") (pintype "passive"))
      (node (ref "T28") (pin "1") (pinfunction "C_1") (pintype "passive"))
    )
    (net (code "56") (name "Net-(T28-E)") (class "Default")
      (node (ref "T28") (pin "3") (pinfunction "E_3") (pintype "passive"))
      (node (ref "T29") (pin "1") (pinfunction "C_1") (pintype "passive"))
    )
    (net (code "57") (name "Net-(T29-B)") (class "Default")
      (node (ref "R43") (pin "2") (pinfunction "2_2") (pintype "passive"))
      (node (ref "T29") (pin "2") (pinfunction "B_2") (pintype "passive"))
    )
    (net (code "58") (name "Net-(T30-B)") (class "Default")
      (node (ref "R45") (pin "2") (pinfunction "2_2") (pintype "passive"))
      (node (ref "T30") (pin "2") (pinfunction "B_2") (pintype "passive"))
    )
    (net (code "59") (name "Net-(T30-C)") (class "Default")
      (node (ref "R47") (pin "1") (pinfunction "1_1") (pintype "passive"))
      (node (ref "R51") (pin "1") (pinfunction "1_1") (pintype "passive"))
      (node (ref "T30") (pin "1") (pinfunction "C_1") (pintype "passive"))
    )
    (net (code "60") (name "Net-(T30-E)") (class "Default")
      (node (ref "T30") (pin "3") (pinfunction "E_3") (pintype "passive"))
      (node (ref "T31") (pin "1") (pinfunction "C_1") (pintype "passive"))
    )
    (net (code "61") (name "Net-(T31-B)") (class "Default")
      (node (ref "R46") (pin "2") (pinfunction "2_2") (pintype "passive"))
      (node (ref "T31") (pin "2") (pinfunction "B_2") (pintype "passive"))
    )
    (net (code "62") (name "Net-(T32-B)") (class "Default")
      (node (ref "R48") (pin "2") (pinfunction "2_2") (pintype "passive"))
      (node (ref "T32") (pin "2") (pinfunction "B_2") (pintype "passive"))
    )
    (net (code "63") (name "Net-(T32-C)") (class "Default")
      (node (ref "R50") (pin "1") (pinfunction "1_1") (pintype "passive"))
      (node (ref "T32") (pin "1") (pinfunction "C_1") (pintype "passive"))
    )
    (net (code "64") (name "Net-(T33-B)") (class "Default")
      (node (ref "R49") (pin "2") (pinfunction "2_2") (pintype "passive"))
      (node (ref "T33") (pin "2") (pinfunction "B_2") (pintype "passive"))
    )
    (net (code "65") (name "Net-(T34-B)") (class "Default")
      (node (ref "R51") (pin "2") (pinfunction "2_2") (pintype "passive"))
      (node (ref "T34") (pin "2") (pinfunction "B_2") (pintype "passive"))
    )
    (net (code "66") (name "Net-(T34-C)") (class "Default")
      (node (ref "R49") (pin "1") (pinfunction "1_1") (pintype "passive"))
      (node (ref "R52") (pin "1") (pinfunction "1_1") (pintype "passive"))
      (node (ref "T34") (pin "1") (pinfunction "C_1") (pintype "passive"))
    )
    (net (code "67") (name "Net-(T35-B)") (class "Default")
      (node (ref "R53") (pin "2") (pinfunction "2_2") (pintype "passive"))
      (node (ref "T35") (pin "2") (pinfunction "B_2") (pintype "passive"))
    )
    (net (code "68") (name "Net-(T35-C)") (class "Default")
      (node (ref "R48") (pin "1") (pinfunction "1_1") (pintype "passive"))
      (node (ref "R54") (pin "1") (pinfunction "1_1") (pintype "passive"))
      (node (ref "T35") (pin "1") (pinfunction "C_1") (pintype "passive"))
    )
    (net (code "69") (name "Net-(T36-B)") (class "Default")
      (node (ref "R55") (pin "2") (pinfunction "2_2") (pintype "passive"))
      (node (ref "T36") (pin "2") (pinfunction "B_2") (pintype "passive"))
    )
    (net (code "70") (name "Net-(T36-C)") (class "Default")
      (node (ref "R57") (pin "1") (pinfunction "1_1") (pintype "passive"))
      (node (ref "R63") (pin "1") (pinfunction "1_1") (pintype "passive"))
      (node (ref "T36") (pin "1") (pinfunction "C_1") (pintype "passive"))
    )
    (net (code "71") (name "Net-(T36-E)") (class "Default")
      (node (ref "T36") (pin "3") (pinfunction "E_3") (pintype "passive"))
      (node (ref "T37") (pin "1") (pinfunction "C_1") (pintype "passive"))
    )
    (net (code "72") (name "Net-(T37-B)") (class "Default")
      (node (ref "R56") (pin "2") (pinfunction "2_2") (pintype "passive"))
      (node (ref "T37") (pin "2") (pinfunction "B_2") (pintype "passive"))
    )
    (net (code "73") (name "Net-(T38-B)") (class "Default")
      (node (ref "R58") (pin "2") (pinfunction "2_2") (pintype "passive"))
      (node (ref "T38") (pin "2") (pinfunction "B_2") (pintype "passive"))
    )
    (net (code "74") (name "Net-(T38-C)") (class "Default")
      (node (ref "R60") (pin "1") (pinfunction "1_1") (pintype "passive"))
      (node (ref "R82") (pin "1") (pinfunction "1_1") (pintype "passive"))
      (node (ref "T38") (pin "1") (pinfunction "C_1") (pintype "passive"))
    )
    (net (code "75") (name "Net-(T38-E)") (class "Default")
      (node (ref "T38") (pin "3") (pinfunction "E_3") (pintype "passive"))
      (node (ref "T39") (pin "1") (pinfunction "C_1") (pintype "passive"))
    )
    (net (code "76") (name "Net-(T39-B)") (class "Default")
      (node (ref "R59") (pin "2") (pinfunction "2_2") (pintype "passive"))
      (node (ref "T39") (pin "2") (pinfunction "B_2") (pintype "passive"))
    )
    (net (code "77") (name "Net-(T40-B)") (class "Default")
      (node (ref "R61") (pin "2") (pinfunction "2_2") (pintype "passive"))
      (node (ref "T40") (pin "2") (pinfunction "B_2") (pintype "passive"))
    )
    (net (code "78") (name "Net-(T40-C)") (class "Default")
      (node (ref "R76") (pin "1") (pinfunction "1_1") (pintype "passive"))
      (node (ref "R80") (pin "1") (pinfunction "1_1") (pintype "passive"))
      (node (ref "T40") (pin "1") (pinfunction "C_1") (pintype "passive"))
    )
    (net (code "79") (name "Net-(T40-E)") (class "Default")
      (node (ref "T40") (pin "3") (pinfunction "E_3") (pintype "passive"))
      (node (ref "T49") (pin "1") (pinfunction "C_1") (pintype "passive"))
    )
    (net (code "80") (name "Net-(T41-B)") (class "Default")
      (node (ref "R63") (pin "2") (pinfunction "2_2") (pintype "passive"))
      (node (ref "T41") (pin "2") (pinfunction "B_2") (pintype "passive"))
    )
    (net (code "81") (name "Net-(T42-B)") (class "Default")
      (node (ref "R65") (pin "2") (pinfunction "2_2") (pintype "passive"))
      (node (ref "T42") (pin "2") (pinfunction "B_2") (pintype "passive"))
    )
    (net (code "82") (name "Net-(T42-C)") (class "Default")
      (node (ref "R27") (pin "1") (pinfunction "1_1") (pintype "passive"))
      (node (ref "R30") (pin "1") (pinfunction "1_1") (pintype "passive"))
      (node (ref "R67") (pin "1") (pinfunction "1_1") (pintype "passive"))
      (node (ref "T42") (pin "1") (pinfunction "C_1") (pintype "passive"))
      (node (ref "T43") (pin "1") (pinfunction "C_1") (pintype "passive"))
      (node (ref "T44") (pin "1") (pinfunction "C_1") (pintype "passive"))
    )
    (net (code "83") (name "Net-(T43-B)") (class "Default")
      (node (ref "R66") (pin "2") (pinfunction "2_2") (pintype "passive"))
      (node (ref "T43") (pin "2") (pinfunction "B_2") (pintype "passive"))
    )
    (net (code "84") (name "Net-(T44-B)") (class "Default")
      (node (ref "R68") (pin "2") (pinfunction "2_2") (pintype "passive"))
      (node (ref "T44") (pin "2") (pinfunction "B_2") (pintype "passive"))
    )
    (net (code "85") (name "Net-(T47-B)") (class "Default")
      (node (ref "R72") (pin "2") (pinfunction "2_2") (pintype "passive"))
      (node (ref "T47") (pin "2") (pinfunction "B_2") (pintype "passive"))
    )
    (net (code "86") (name "Net-(T47-C)") (class "Default")
      (node (ref "R5") (pin "1") (pinfunction "1_1") (pintype "passive"))
      (node (ref "R74") (pin "1") (pinfunction "1_1") (pintype "passive"))
      (node (ref "T47") (pin "1") (pinfunction "C_1") (pintype "passive"))
    )
    (net (code "87") (name "Net-(T49-B)") (class "Default")
      (node (ref "R62") (pin "2") (pinfunction "2_2") (pintype "passive"))
      (node (ref "T49") (pin "2") (pinfunction "B_2") (pintype "passive"))
    )
    (net (code "88") (name "Net-(T50-B)") (class "Default")
      (node (ref "R77") (pin "2") (pinfunction "2_2") (pintype "passive"))
      (node (ref "T50") (pin "2") (pinfunction "B_2") (pintype "passive"))
    )
    (net (code "89") (name "Net-(T50-C)") (class "Default")
      (node (ref "R79") (pin "1") (pinfunction "1_1") (pintype "passive"))
      (node (ref "T50") (pin "1") (pinfunction "C_1") (pintype "passive"))
    )
    (net (code "90") (name "Net-(T51-B)") (class "Default")
      (node (ref "R78") (pin "2") (pinfunction "2_2") (pintype "passive"))
      (node (ref "T51") (pin "2") (pinfunction "B_2") (pintype "passive"))
    )
    (net (code "91") (name "Net-(T52-B)") (class "Default")
      (node (ref "R80") (pin "2") (pinfunction "2_2") (pintype "passive"))
      (node (ref "T52") (pin "2") (pinfunction "B_2") (pintype "passive"))
    )
    (net (code "92") (name "Net-(T52-C)") (class "Default")
      (node (ref "R78") (pin "1") (pinfunction "1_1") (pintype "passive"))
      (node (ref "R81") (pin "1") (pinfunction "1_1") (pintype "passive"))
      (node (ref "T52") (pin "1") (pinfunction "C_1") (pintype "passive"))
    )
    (net (code "93") (name "Net-(T53-B)") (class "Default")
      (node (ref "R82") (pin "2") (pinfunction "2_2") (pintype "passive"))
      (node (ref "T53") (pin "2") (pinfunction "B_2") (pintype "passive"))
    )
    (net (code "94") (name "Net-(T53-C)") (class "Default")
      (node (ref "R77") (pin "1") (pinfunction "1_1") (pintype "passive"))
      (node (ref "R83") (pin "1") (pinfunction "1_1") (pintype "passive"))
      (node (ref "T53") (pin "1") (pinfunction "C_1") (pintype "passive"))
    )
    (net (code "95") (name "Net-(T65-B)") (class "Default")
      (node (ref "R95") (pin "2") (pinfunction "2_2") (pintype "passive"))
      (node (ref "T65") (pin "2") (pinfunction "B_2") (pintype "passive"))
    )
    (net (code "96") (name "Net-(T65-C)") (class "Default")
      (node (ref "T65") (pin "1") (pinfunction "C_1") (pintype "passive"))
      (node (ref "VALUE") (pin "K") (pinfunction "C_K") (pintype "passive"))
    )
    (net (code "97") (name "OUT") (class "Default")
      (node (ref "T32") (pin "3") (pinfunction "E_3") (pintype "passive"))
      (node (ref "T33") (pin "1") (pinfunction "C_1") (pintype "passive"))
      (node (ref "X3") (pin "2") (pinfunction "S_2") (pintype "passive"))
    )
    (net (code "98") (name "OUT2") (class "Default")
      (node (ref "T50") (pin "3") (pinfunction "E_3") (pintype "passive"))
      (node (ref "T51") (pin "1") (pinfunction "C_1") (pintype "passive"))
      (node (ref "X3") (pin "4") (pinfunction "S_4") (pintype "passive"))
    )
    (net (code "99") (name "RESET") (class "Default")
      (node (ref "R23") (pin "1") (pinfunction "1_1") (pintype "passive"))
      (node (ref "R66") (pin "1") (pinfunction "1_1") (pintype "passive"))
      (node (ref "X2") (pin "4") (pinfunction "S_4") (pintype "passive"))
    )
    (net (code "100") (name "UP") (class "Default")
      (node (ref "R10") (pin "1") (pinfunction "1_1") (pintype "passive"))
      (node (ref "R55") (pin "1") (pinfunction "1_1") (pintype "passive"))
      (node (ref "R68") (pin "1") (pinfunction "1_1") (pintype "passive"))
      (node (ref "R8") (pin "1") (pinfunction "1_1") (pintype "passive"))
      (node (ref "X2") (pin "5") (pinfunction "S_5") (pintype "passive"))
    )
    (net (code "101") (name "VALUE") (class "Default")
      (node (ref "R11") (pin "1") (pinfunction "1_1") (pintype "passive"))
      (node (ref "R38") (pin "1") (pinfunction "1_1") (pintype "passive"))
      (node (ref "R39") (pin "1") (pinfunction "1_1") (pintype "passive"))
      (node (ref "R42") (pin "1") (pinfunction "1_1") (pintype "passive"))
      (node (ref "R56") (pin "1") (pinfunction "1_1") (pintype "passive"))
      (node (ref "R58") (pin "1") (pinfunction "1_1") (pintype "passive"))
      (node (ref "R95") (pin "1") (pinfunction "1_1") (pintype "passive"))
      (node (ref "T23") (pin "1") (pinfunction "C_1") (pintype "passive"))
      (node (ref "T25") (pin "1") (pinfunction "C_1") (pintype "passive"))
      (node (ref "X3") (pin "5") (pinfunction "S_5") (pintype "passive"))
    )
    (net (code "102") (name "VCC") (class "Default")
      (node (ref "R12") (pin "2") (pinfunction "2_2") (pintype "passive"))
      (node (ref "R15") (pin "2") (pinfunction "2_2") (pintype "passive"))
      (node (ref "R18") (pin "2") (pinfunction "2_2") (pintype "passive"))
      (node (ref "R21") (pin "2") (pinfunction "2_2") (pintype "passive"))
      (node (ref "R24") (pin "2") (pinfunction "2_2") (pintype "passive"))
      (node (ref "R28") (pin "2") (pinfunction "2_2") (pintype "passive"))
      (node (ref "R3") (pin "2") (pinfunction "2_2") (pintype "passive"))
      (node (ref "R31") (pin "2") (pinfunction "2_2") (pintype "passive"))
      (node (ref "R34") (pin "2") (pinfunction "2_2") (pintype "passive"))
      (node (ref "R37") (pin "2") (pinfunction "2_2") (pintype "passive"))
      (node (ref "R38") (pin "2") (pinfunction "2_2") (pintype "passive"))
      (node (ref "R41") (pin "2") (pinfunction "2_2") (pintype "passive"))
      (node (ref "R44") (pin "2") (pinfunction "2_2") (pintype "passive"))
      (node (ref "R47") (pin "2") (pinfunction "2_2") (pintype "passive"))
      (node (ref "R50") (pin "2") (pinfunction "2_2") (pintype "passive"))
      (node (ref "R52") (pin "2") (pinfunction "2_2") (pintype "passive"))
      (node (ref "R54") (pin "2") (pinfunction "2_2") (pintype "passive"))
      (node (ref "R57") (pin "2") (pinfunction "2_2") (pintype "passive"))
      (node (ref "R6") (pin "2") (pinfunction "2_2") (pintype "passive"))
      (node (ref "R60") (pin "2") (pinfunction "2_2") (pintype "passive"))
      (node (ref "R64") (pin "2") (pinfunction "2_2") (pintype "passive"))
      (node (ref "R67") (pin "2") (pinfunction "2_2") (pintype "passive"))
      (node (ref "R74") (pin "2") (pinfunction "2_2") (pintype "passive"))
      (node (ref "R76") (pin "2") (pinfunction "2_2") (pintype "passive"))
      (node (ref "R79") (pin "2") (pinfunction "2_2") (pintype "passive"))
      (node (ref "R81") (pin "2") (pinfunction "2_2") (pintype "passive"))
      (node (ref "R83") (pin "2") (pinfunction "2_2") (pintype "passive"))
      (node (ref "R9") (pin "2") (pinfunction "2_2") (pintype "passive"))
      (node (ref "R96") (pin "2") (pinfunction "2_2") (pintype "passive"))
      (node (ref "X2") (pin "1") (pinfunction "S_1") (pintype "passive"))
    )
    (net (code "103") (name "WE") (class "Default")
      (node (ref "R43") (pin "1") (pinfunction "1_1") (pintype "passive"))
      (node (ref "R45") (pin "1") (pinfunction "1_1") (pintype "passive"))
      (node (ref "X3") (pin "1") (pinfunction "S_1") (pintype "passive"))
    )
    (net (code "104") (name "WE2") (class "Default")
      (node (ref "R59") (pin "1") (pinfunction "1_1") (pintype "passive"))
      (node (ref "R61") (pin "1") (pinfunction "1_1") (pintype "passive"))
      (node (ref "X3") (pin "3") (pinfunction "S_3") (pintype "passive"))
    )
  )
)
